# Main_-_Wide_ESP.net
KiCad netlist of a schematic drawn in EAGLE
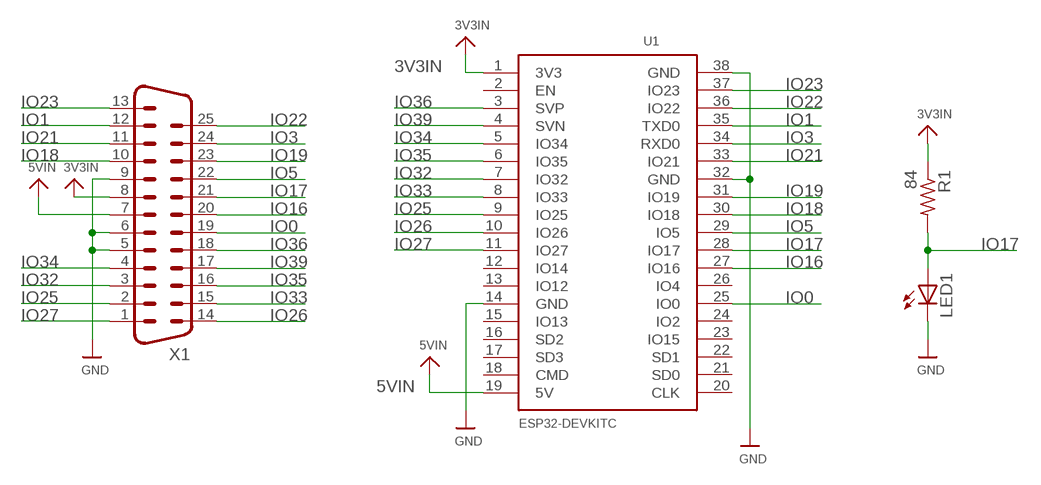
[diagram p0: schematic, sheet 1]

(export (version "E")
  (design (tool "Eeschema 10.0.6"))
  (components
    (comp (ref "LED1")
      (value "LEDCHIPLED_1206")
      (footprint "eagle-import:CHIPLED_1206")
      (libsource (lib "eagle-import") (part "LEDCHIPLED_1206"))
    )
    (comp (ref "R1")
      (value "84")
      (footprint "eagle-import:R1206")
      (libsource (lib "eagle-import") (part "R-US_R1206"))
    )
    (comp (ref "U1")
      (value "ESP32DEVKITC")
      (footprint "eagle-import:ESP32-DEVKITC")
      (libsource (lib "eagle-import") (part "ESP32DEVKITC"))
    )
    (comp (ref "X1")
      (value "DB25_MALEH")
      (footprint "eagle-import:M25H")
      (libsource (lib "eagle-import") (part "DB25_MALEH"))
    )
  )
  (nets
    (net (code "1") (name "/IO0") (class "Default")
      (node (ref "U1") (pin "25") (pinfunction "IO0_25") (pintype "bidirectional"))
      (node (ref "X1") (pin "19") (pinfunction "19_19") (pintype "passive"))
    )
    (net (code "2") (name "/IO1") (class "Default")
      (node (ref "U1") (pin "35") (pinfunction "TXD0_35") (pintype "bidirectional"))
      (node (ref "X1") (pin "12") (pinfunction "12_12") (pintype "passive"))
    )
    (net (code "3") (name "/IO3") (class "Default")
      (node (ref "U1") (pin "34") (pinfunction "RXD0_34") (pintype "bidirectional"))
      (node (ref "X1") (pin "24") (pinfunction "24_24") (pintype "passive"))
    )
    (net (code "4") (name "/IO5") (class "Default")
      (node (ref "U1") (pin "29") (pinfunction "IO5_29") (pintype "bidirectional"))
      (node (ref "X1") (pin "22") (pinfunction "22_22") (pintype "passive"))
    )
    (net (code "5") (name "/IO16") (class "Default")
      (node (ref "U1") (pin "27") (pinfunction "IO16_27") (pintype "bidirectional"))
      (node (ref "X1") (pin "20") (pinfunction "20_20") (pintype "passive"))
    )
    (net (code "6") (name "/IO17") (class "Default")
      (node (ref "LED1") (pin "A") (pinfunction "A_A") (pintype "passive"))
      (node (ref "R1") (pin "2") (pinfunction "2_2") (pintype "passive"))
      (node (ref "U1") (pin "28") (pinfunction "IO17_28") (pintype "bidirectional"))
      (node (ref "X1") (pin "21") (pinfunction "21_21") (pintype "passive"))
    )
    (net (code "7") (name "/IO18") (class "Default")
      (node (ref "U1") (pin "30") (pinfunction "IO18_30") (pintype "bidirectional"))
      (node (ref "X1") (pin "10") (pinfunction "10_10") (pintype "passive"))
    )
    (net (code "8") (name "/IO19") (class "Default")
      (node (ref "U1") (pin "31") (pinfunction "IO19_31") (pintype "bidirectional"))
      (node (ref "X1") (pin "23") (pinfunction "23_23") (pintype "passive"))
    )
    (net (code "9") (name "/IO21") (class "Default")
      (node (ref "U1") (pin "33") (pinfunction "IO21_33") (pintype "bidirectional"))
      (node (ref "X1") (pin "11") (pinfunction "11_11") (pintype "passive"))
    )
    (net (code "10") (name "/IO22") (class "Default")
      (node (ref "U1") (pin "36") (pinfunction "IO22_36") (pintype "bidirectional"))
      (node (ref "X1") (pin "25") (pinfunction "25_25") (pintype "passive"))
    )
    (net (code "11") (name "/IO23") (class "Default")
      (node (ref "U1") (pin "37") (pinfunction "IO23_37") (pintype "bidirectional"))
      (node (ref "X1") (pin "13") (pinfunction "13_13") (pintype "passive"))
    )
    (net (code "12") (name "/IO25") (class "Default")
      (node (ref "U1") (pin "9") (pinfunction "IO25_9") (pintype "bidirectional"))
      (node (ref "X1") (pin "2") (pinfunction "2_2") (pintype "passive"))
    )
    (net (code "13") (name "/IO26") (class "Default")
      (node (ref "U1") (pin "10") (pinfunction "IO26_10") (pintype "bidirectional"))
      (node (ref "X1") (pin "14") (pinfunction "14_14") (pintype "passive"))
    )
    (net (code "14") (name "/IO27") (class "Default")
      (node (ref "U1") (pin "11") (pinfunction "IO27_11") (pintype "bidirectional"))
      (node (ref "X1") (pin "1") (pinfunction "1_1") (pintype "passive"))
    )
    (net (code "15") (name "/IO32") (class "Default")
      (node (ref "U1") (pin "7") (pinfunction "IO32_7") (pintype "bidirectional"))
      (node (ref "X1") (pin "3") (pinfunction "3_3") (pintype "passive"))
    )
    (net (code "16") (name "/IO33") (class "Default")
      (node (ref "U1") (pin "8") (pinfunction "IO33_8") (pintype "bidirectional"))
      (node (ref "X1") (pin "15") (pinfunction "15_15") (pintype "passive"))
    )
    (net (code "17") (name "/IO34") (class "Default")
      (node (ref "U1") (pin "5") (pinfunction "IO34_5") (pintype "bidirectional"))
      (node (ref "X1") (pin "4") (pinfunction "4_4") (pintype "passive"))
    )
    (net (code "18") (name "/IO35") (class "Default")
      (node (ref "U1") (pin "6") (pinfunction "IO35_6") (pintype "bidirectional"))
      (node (ref "X1") (pin "16") (pinfunction "16_16") (pintype "passive"))
    )
    (net (code "19") (name "/IO36") (class "Default")
      (node (ref "U1") (pin "3") (pinfunction "SVP_3") (pintype "bidirectional"))
      (node (ref "X1") (pin "18") (pinfunction "18_18") (pintype "passive"))
    )
    (net (code "20") (name "/IO39") (class "Default")
      (node (ref "U1") (pin "4") (pinfunction "SVN_4") (pintype "bidirectional"))
      (node (ref "X1") (pin "17") (pinfunction "17_17") (pintype "passive"))
    )
    (net (code "21") (name "3V3IN") (class "Default")
      (node (ref "R1") (pin "1") (pinfunction "1_1") (pintype "passive"))
      (node (ref "U1") (pin "1") (pinfunction "3V3_1") (pintype "bidirectional"))
      (node (ref "X1") (pin "8") (pinfunction "8_8") (pintype "passive"))
    )
    (net (code "22") (name "5VIN") (class "Default")
      (node (ref "U1") (pin "19") (pinfunction "5V_19") (pintype "bidirectional"))
      (node (ref "X1") (pin "7") (pinfunction "7_7") (pintype "passive"))
    )
    (net (code "23") (name "GND") (class "Default")
      (node (ref "LED1") (pin "C") (pinfunction "C_C") (pintype "passive"))
      (node (ref "U1") (pin "14") (pinfunction "GND_14") (pintype "bidirectional"))
      (node (ref "U1") (pin "32") (pinfunction "GND_32") (pintype "bidirectional"))
      (node (ref "U1") (pin "38") (pinfunction "GND_38") (pintype "bidirectional"))
      (node (ref "X1") (pin "5") (pinfunction "5_5") (pintype "passive"))
      (node (ref "X1") (pin "6") (pinfunction "6_6") (pintype "passive"))
      (node (ref "X1") (pin "9") (pinfunction "9_9") (pintype "passive"))
    )
    (net (code "24") (name "unconnected-(U1-CLK-Pad20)") (class "Default")
      (node (ref "U1") (pin "20") (pinfunction "CLK_20") (pintype "bidirectional"))
    )
    (net (code "25") (name "unconnected-(U1-CMD-Pad18)") (class "Default")
      (node (ref "U1") (pin "18") (pinfunction "CMD_18") (pintype "bidirectional"))
    )
    (net (code "26") (name "unconnected-(U1-EN-Pad2)") (class "Default")
      (node (ref "U1") (pin "2") (pinfunction "EN_2") (pintype "bidirectional"))
    )
    (net (code "27") (name "unconnected-(U1-IO2-Pad24)") (class "Default")
      (node (ref "U1") (pin "24") (pinfunction "IO2_24") (pintype "bidirectional"))
    )
    (net (code "28") (name "unconnected-(U1-IO4-Pad26)") (class "Default")
      (node (ref "U1") (pin "26") (pinfunction "IO4_26") (pintype "bidirectional"))
    )
    (net (code "29") (name "unconnected-(U1-IO12-Pad13)") (class "Default")
      (node (ref "U1") (pin "13") (pinfunction "IO12_13") (pintype "bidirectional"))
    )
    (net (code "30") (name "unconnected-(U1-IO13-Pad15)") (class "Default")
      (node (ref "U1") (pin "15") (pinfunction "IO13_15") (pintype "bidirectional"))
    )
    (net (code "31") (name "unconnected-(U1-IO14-Pad12)") (class "Default")
      (node (ref "U1") (pin "12") (pinfunction "IO14_12") (pintype "bidirectional"))
    )
    (net (code "32") (name "unconnected-(U1-IO15-Pad23)") (class "Default")
      (node (ref "U1") (pin "23") (pinfunction "IO15_23") (pintype "bidirectional"))
    )
    (net (code "33") (name "unconnected-(U1-SD0-Pad21)") (class "Default")
      (node (ref "U1") (pin "21") (pinfunction "SD0_21") (pintype "bidirectional"))
    )
    (net (code "34") (name "unconnected-(U1-SD1-Pad22)") (class "Default")
      (node (ref "U1") (pin "22") (pinfunction "SD1_22") (pintype "bidirectional"))
    )
    (net (code "35") (name "unconnected-(U1-SD2-Pad16)") (class "Default")
      (node (ref "U1") (pin "16") (pinfunction "SD2_16") (pintype "bidirectional"))
    )
    (net (code "36") (name "unconnected-(U1-SD3-Pad17)") (class "Default")
      (node (ref "U1") (pin "17") (pinfunction "SD3_17") (pintype "bidirectional"))
    )
  )
)
